# BAT.net
KiCad netlist of a schematic drawn in Altium Designer
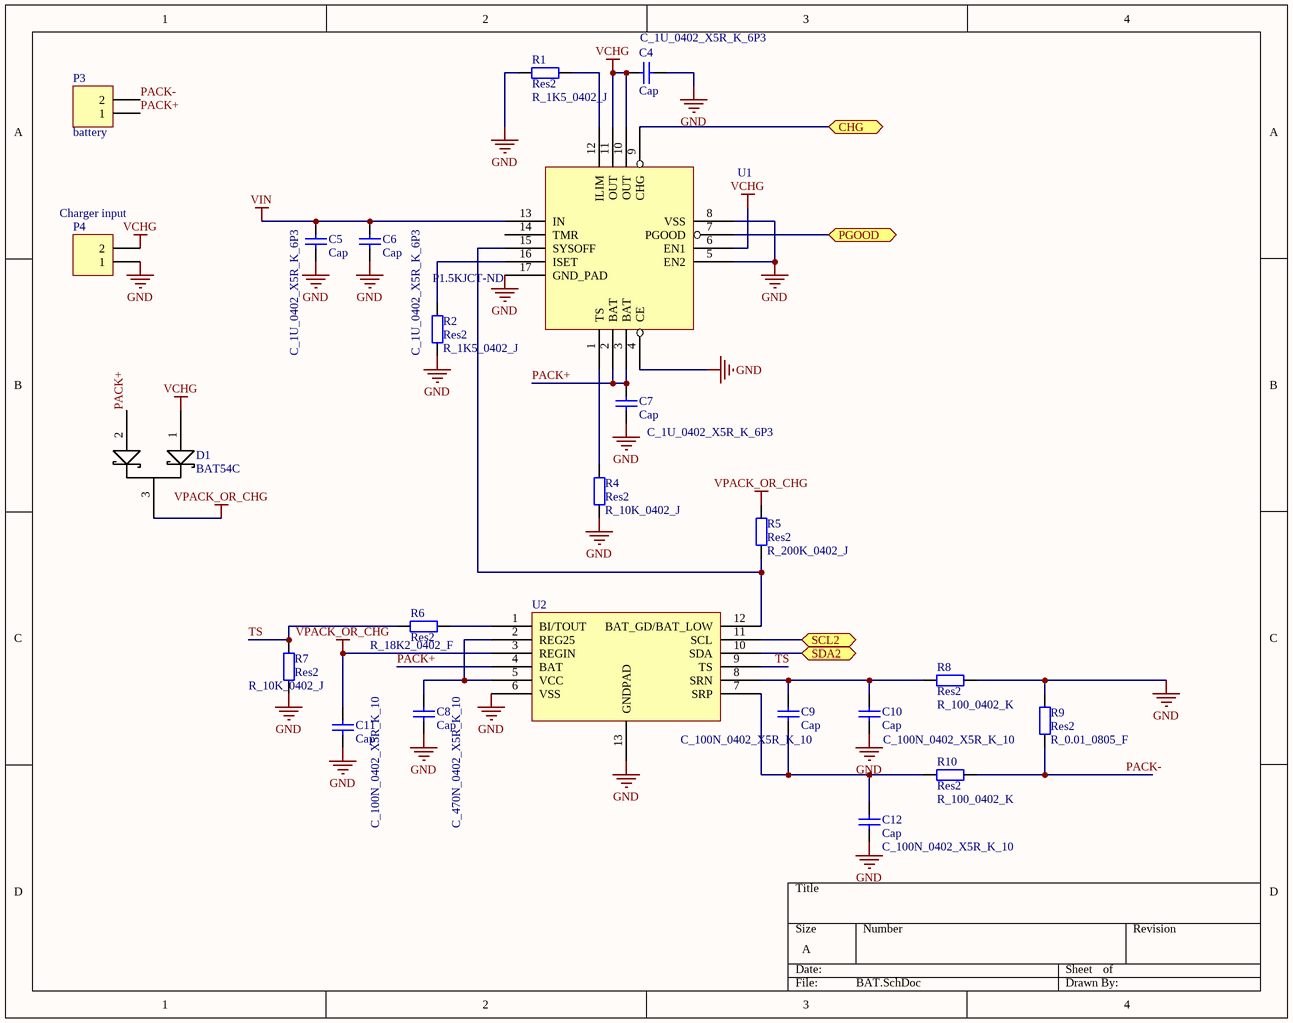
[diagram p0: BAT.SchDoc]

(export (version "E")
  (design (tool "Eeschema 10.0.6"))
  (components
    (comp (ref "C4")
      (value "Cap")
      (footprint "C_0402")
      (description "Capacitor")
      (fields (field (name "ALTIUM_VALUE") "C_1U_0402_X5R_K_6P3") (field (name "PUBLISHER") "Altium Limited"))
      (libsource (lib "Miscellaneous Devices") (part "Cap"))
    )
    (comp (ref "C5")
      (value "Cap")
      (footprint "C_0402")
      (description "Capacitor")
      (fields (field (name "ALTIUM_VALUE") "C_1U_0402_X5R_K_6P3") (field (name "PUBLISHER") "Altium Limited"))
      (libsource (lib "Miscellaneous Devices") (part "Cap"))
    )
    (comp (ref "C6")
      (value "Cap")
      (footprint "C_0402")
      (description "Capacitor")
      (fields (field (name "ALTIUM_VALUE") "C_1U_0402_X5R_K_6P3") (field (name "PUBLISHER") "Altium Limited"))
      (libsource (lib "Miscellaneous Devices") (part "Cap"))
    )
    (comp (ref "C7")
      (value "Cap")
      (footprint "C_0402")
      (description "Capacitor")
      (fields (field (name "ALTIUM_VALUE") "C_1U_0402_X5R_K_6P3") (field (name "PUBLISHER") "Altium Limited"))
      (libsource (lib "Miscellaneous Devices") (part "Cap"))
    )
    (comp (ref "C8")
      (value "Cap")
      (footprint "C_0402")
      (description "Capacitor")
      (fields
        (field (name "ALTIUM_VALUE") "C_470N_0402_X5R_K_10")
        (field (name "PUBLISHER") "Altium Limited")
      )
      (libsource (lib "Miscellaneous Devices") (part "Cap"))
    )
    (comp (ref "C9")
      (value "Cap")
      (footprint "C_0402")
      (description "Capacitor")
      (fields
        (field (name "ALTIUM_VALUE") "C_100N_0402_X5R_K_10")
        (field (name "PUBLISHER") "Altium Limited")
      )
      (libsource (lib "Miscellaneous Devices") (part "Cap"))
    )
    (comp (ref "C10")
      (value "Cap")
      (footprint "C_0402")
      (description "Capacitor")
      (fields
        (field (name "ALTIUM_VALUE") "C_100N_0402_X5R_K_10")
        (field (name "PUBLISHER") "Altium Limited")
      )
      (libsource (lib "Miscellaneous Devices") (part "Cap"))
    )
    (comp (ref "C11")
      (value "Cap")
      (footprint "C_0402")
      (description "Capacitor")
      (fields
        (field (name "ALTIUM_VALUE") "C_100N_0402_X5R_K_10")
        (field (name "PUBLISHER") "Altium Limited")
      )
      (libsource (lib "Miscellaneous Devices") (part "Cap"))
    )
    (comp (ref "C12")
      (value "Cap")
      (footprint "C_0402")
      (description "Capacitor")
      (fields
        (field (name "ALTIUM_VALUE") "C_100N_0402_X5R_K_10")
        (field (name "PUBLISHER") "Altium Limited")
      )
      (libsource (lib "Miscellaneous Devices") (part "Cap"))
    )
    (comp (ref "D1")
      (value "BAT54C")
      (footprint "SOT-23_N")
      (description "FAIRCHILD SEMICONDUCTOR - BAT54C - SCHOTTKY RECTIFIER, CMN CTHD 0.2A SOT-23")
      (fields (field (name "MANUFACTURER") "FAIRCHILD SEMICONDUCTOR"))
      (libsource (lib "BrewBit") (part "BAT54C"))
    )
    (comp (ref "P3")
      (value "battery")
      (footprint "PL-041939")
      (description "Header, 2-Pin")
      (fields (field (name "PUBLISHER") "Altium Limited"))
      (libsource (lib "Miscellaneous Connectors") (part "Header 2"))
    )
    (comp (ref "P4")
      (value "Charger input")
      (footprint "HDR1X2")
      (description "SM Battery Holder 1/2 AA")
      (fields (field (name "PUBLISHER") "Altium Limited"))
      (libsource (lib "Miscellaneous Connectors") (part "Header 2"))
    )
    (comp (ref "R1")
      (value "Res2")
      (footprint "R_0402")
      (description "Resistor")
      (fields (field (name "ALTIUM_VALUE") "R_1K5_0402_J") (field (name "PUBLISHER") "Altium Limited"))
      (libsource (lib "") (part "Res2_1"))
    )
    (comp (ref "R2")
      (value "Res2")
      (footprint "R_0402")
      (description "Resistor")
      (fields
        (field (name "ALTIUM_VALUE") "R_1K5_0402_J")
        (field (name "SUPPLIER PART NUMBER 1") "P1.5KJCT-ND")
        (field (name "PUBLISHER") "Altium Limited")
      )
      (libsource (lib "") (part "Res2_2"))
    )
    (comp (ref "R4")
      (value "Res2")
      (footprint "R_0402")
      (description "Resistor")
      (fields (field (name "ALTIUM_VALUE") "R_10K_0402_J") (field (name "PUBLISHER") "Altium Limited"))
      (libsource (lib "Miscellaneous Devices") (part "Res2"))
    )
    (comp (ref "R5")
      (value "Res2")
      (footprint "R_0402")
      (description "Resistor")
      (fields (field (name "ALTIUM_VALUE") "R_200K_0402_J") (field (name "PUBLISHER") "Altium Limited"))
      (libsource (lib "") (part "Res2_2"))
    )
    (comp (ref "R6")
      (value "Res2")
      (footprint "R_0402")
      (description "Resistor")
      (fields (field (name "ALTIUM_VALUE") "R_18K2_0402_F") (field (name "PUBLISHER") "Altium Limited"))
      (libsource (lib "") (part "Res2_1"))
    )
    (comp (ref "R7")
      (value "Res2")
      (footprint "R_0402")
      (description "Resistor")
      (fields (field (name "ALTIUM_VALUE") "R_10K_0402_J") (field (name "PUBLISHER") "Altium Limited"))
      (libsource (lib "Miscellaneous Devices") (part "Res2"))
    )
    (comp (ref "R8")
      (value "Res2")
      (footprint "R_0402")
      (description "Resistor")
      (fields (field (name "ALTIUM_VALUE") "R_100_0402_K") (field (name "PUBLISHER") "Altium Limited"))
      (libsource (lib "") (part "Res2_1"))
    )
    (comp (ref "R9")
      (value "Res2")
      (footprint "R_0805")
      (description "Resistor")
      (fields
        (field (name "ALTIUM_VALUE") "R_0.01_0805_F")
        (field (name "MANUFACTURER") "Panasonic Electronic Components")
        (field (name "MANUFACTURER PART NUMBER") "ERJ-6BWFR010V")
        (field (name "PUBLISHER") "Altium Limited")
      )
      (libsource (lib "Miscellaneous Devices") (part "Res2"))
    )
    (comp (ref "R10")
      (value "Res2")
      (footprint "R_0402")
      (description "Resistor")
      (fields (field (name "ALTIUM_VALUE") "R_100_0402_K") (field (name "PUBLISHER") "Altium Limited"))
      (libsource (lib "") (part "Res2_1"))
    )
    (comp (ref "U1")
      (value "BQ24079TRGTR")
      (footprint "S-PVQFN-N16")
      (description "IC LI-ION CHARGE/PWR MGMT 16QFN")
      (fields (field (name "MANUFACTURER") "Texas Instruments"))
      (libsource (lib "BrewBit") (part "BQ24079TRGTR"))
    )
    (comp (ref "U2")
      (value "BQ27510DRZR-G2")
      (footprint "S-PDSO-N12")
      (description "IC BATT FUEL GAUGE LI-ION 12SON")
      (fields (field (name "MANUFACTURER") "Texas Instruments"))
      (libsource (lib "BrewBit") (part "BQ27510DRZR-G2"))
    )
  )
  (nets
    (net (code "1") (name "/CHG") (class "Default")
      (node (ref "U1") (pin "9") (pinfunction "CHG_9") (pintype "passive"))
    )
    (net (code "2") (name "/PACK+") (class "Default")
      (node (ref "C7") (pin "2") (pinfunction "2_2") (pintype "passive"))
      (node (ref "D1") (pin "2") (pinfunction "2_2") (pintype "passive"))
      (node (ref "P3") (pin "1") (pinfunction "1_1") (pintype "passive"))
      (node (ref "U1") (pin "2") (pinfunction "BAT_2") (pintype "passive"))
      (node (ref "U1") (pin "3") (pinfunction "BAT_3") (pintype "passive"))
      (node (ref "U2") (pin "4") (pinfunction "BAT_4") (pintype "passive"))
    )
    (net (code "3") (name "/PACK-") (class "Default")
      (node (ref "P3") (pin "2") (pinfunction "2_2") (pintype "passive"))
      (node (ref "R10") (pin "2") (pinfunction "2_2") (pintype "passive"))
      (node (ref "R9") (pin "1") (pinfunction "1_1") (pintype "passive"))
    )
    (net (code "4") (name "/PGOOD") (class "Default")
      (node (ref "U1") (pin "7") (pinfunction "PGOOD_7") (pintype "passive"))
    )
    (net (code "5") (name "/SCL2") (class "Default")
      (node (ref "U2") (pin "11") (pinfunction "SCL_11") (pintype "passive"))
    )
    (net (code "6") (name "/SDA2") (class "Default")
      (node (ref "U2") (pin "10") (pinfunction "SDA_10") (pintype "passive"))
    )
    (net (code "7") (name "/TS") (class "Default")
      (node (ref "R6") (pin "1") (pinfunction "1_1") (pintype "passive"))
      (node (ref "R7") (pin "2") (pinfunction "2_2") (pintype "passive"))
      (node (ref "U2") (pin "9") (pinfunction "TS_9") (pintype "passive"))
    )
    (net (code "8") (name "GND") (class "Default")
      (node (ref "C10") (pin "1") (pinfunction "1_1") (pintype "passive"))
      (node (ref "C11") (pin "1") (pinfunction "1_1") (pintype "passive"))
      (node (ref "C12") (pin "1") (pinfunction "1_1") (pintype "passive"))
      (node (ref "C4") (pin "1") (pinfunction "1_1") (pintype "passive"))
      (node (ref "C5") (pin "1") (pinfunction "1_1") (pintype "passive"))
      (node (ref "C6") (pin "1") (pinfunction "1_1") (pintype "passive"))
      (node (ref "C7") (pin "1") (pinfunction "1_1") (pintype "passive"))
      (node (ref "C8") (pin "1") (pinfunction "1_1") (pintype "passive"))
      (node (ref "P4") (pin "1") (pinfunction "1_1") (pintype "passive"))
      (node (ref "R1") (pin "1") (pinfunction "1_1") (pintype "passive"))
      (node (ref "R2") (pin "2") (pinfunction "2_2") (pintype "passive"))
      (node (ref "R4") (pin "1") (pinfunction "1_1") (pintype "passive"))
      (node (ref "R7") (pin "1") (pinfunction "1_1") (pintype "passive"))
      (node (ref "R8") (pin "2") (pinfunction "2_2") (pintype "passive"))
      (node (ref "R9") (pin "2") (pinfunction "2_2") (pintype "passive"))
      (node (ref "U1") (pin "17") (pinfunction "GND_PAD_17") (pintype "passive"))
      (node (ref "U1") (pin "4") (pinfunction "CE_4") (pintype "passive"))
      (node (ref "U1") (pin "5") (pinfunction "EN2_5") (pintype "passive"))
      (node (ref "U1") (pin "8") (pinfunction "VSS_8") (pintype "passive"))
      (node (ref "U2") (pin "13") (pinfunction "GNDPAD_13") (pintype "passive"))
      (node (ref "U2") (pin "6") (pinfunction "VSS_6") (pintype "passive"))
    )
    (net (code "9") (name "Net-(U1-ILIM)") (class "Default")
      (node (ref "R1") (pin "2") (pinfunction "2_2") (pintype "passive"))
      (node (ref "U1") (pin "12") (pinfunction "ILIM_12") (pintype "passive"))
    )
    (net (code "10") (name "Net-(U1-ISET)") (class "Default")
      (node (ref "R2") (pin "1") (pinfunction "1_1") (pintype "passive"))
      (node (ref "U1") (pin "16") (pinfunction "ISET_16") (pintype "passive"))
    )
    (net (code "11") (name "Net-(U1-SYSOFF)") (class "Default")
      (node (ref "R5") (pin "2") (pinfunction "2_2") (pintype "passive"))
      (node (ref "U1") (pin "15") (pinfunction "SYSOFF_15") (pintype "passive"))
      (node (ref "U2") (pin "12") (pinfunction "BAT_GD/BAT_LOW_12") (pintype "passive"))
    )
    (net (code "12") (name "Net-(U1-TS)") (class "Default")
      (node (ref "R4") (pin "2") (pinfunction "2_2") (pintype "passive"))
      (node (ref "U1") (pin "1") (pinfunction "TS_1") (pintype "passive"))
    )
    (net (code "13") (name "Net-(U2-BI{slash}TOUT)") (class "Default")
      (node (ref "R6") (pin "2") (pinfunction "2_2") (pintype "passive"))
      (node (ref "U2") (pin "1") (pinfunction "BI/TOUT_1") (pintype "passive"))
    )
    (net (code "14") (name "Net-(U2-REG25)") (class "Default")
      (node (ref "C8") (pin "2") (pinfunction "2_2") (pintype "passive"))
      (node (ref "U2") (pin "2") (pinfunction "REG25_2") (pintype "passive"))
      (node (ref "U2") (pin "5") (pinfunction "VCC_5") (pintype "passive"))
    )
    (net (code "15") (name "Net-(U2-SRN)") (class "Default")
      (node (ref "C10") (pin "2") (pinfunction "2_2") (pintype "passive"))
      (node (ref "C9") (pin "2") (pinfunction "2_2") (pintype "passive"))
      (node (ref "R8") (pin "1") (pinfunction "1_1") (pintype "passive"))
      (node (ref "U2") (pin "8") (pinfunction "SRN_8") (pintype "passive"))
    )
    (net (code "16") (name "Net-(U2-SRP)") (class "Default")
      (node (ref "C12") (pin "2") (pinfunction "2_2") (pintype "passive"))
      (node (ref "C9") (pin "1") (pinfunction "1_1") (pintype "passive"))
      (node (ref "R10") (pin "1") (pinfunction "1_1") (pintype "passive"))
      (node (ref "U2") (pin "7") (pinfunction "SRP_7") (pintype "passive"))
    )
    (net (code "17") (name "VCHG") (class "Default")
      (node (ref "C4") (pin "2") (pinfunction "2_2") (pintype "passive"))
      (node (ref "D1") (pin "1") (pinfunction "1_1") (pintype "passive"))
      (node (ref "P4") (pin "2") (pinfunction "2_2") (pintype "passive"))
      (node (ref "U1") (pin "10") (pinfunction "OUT_10") (pintype "passive"))
      (node (ref "U1") (pin "11") (pinfunction "OUT_11") (pintype "passive"))
      (node (ref "U1") (pin "6") (pinfunction "EN1_6") (pintype "passive"))
    )
    (net (code "18") (name "VIN") (class "Default")
      (node (ref "C5") (pin "2") (pinfunction "2_2") (pintype "passive"))
      (node (ref "C6") (pin "2") (pinfunction "2_2") (pintype "passive"))
      (node (ref "U1") (pin "13") (pinfunction "IN_13") (pintype "passive"))
    )
    (net (code "19") (name "VPACK_OR_CHG") (class "Default")
      (node (ref "C11") (pin "2") (pinfunction "2_2") (pintype "passive"))
      (node (ref "D1") (pin "3") (pinfunction "3_3") (pintype "passive"))
      (node (ref "R5") (pin "1") (pinfunction "1_1") (pintype "passive"))
      (node (ref "U2") (pin "3") (pinfunction "REGIN_3") (pintype "passive"))
    )
    (net (code "20") (name "unconnected-(U1-TMR-Pad14)") (class "Default")
      (node (ref "U1") (pin "14") (pinfunction "TMR_14") (pintype "passive"))
    )
  )
)
